# VCF.net
KiCad netlist of a schematic drawn in Altium Designer
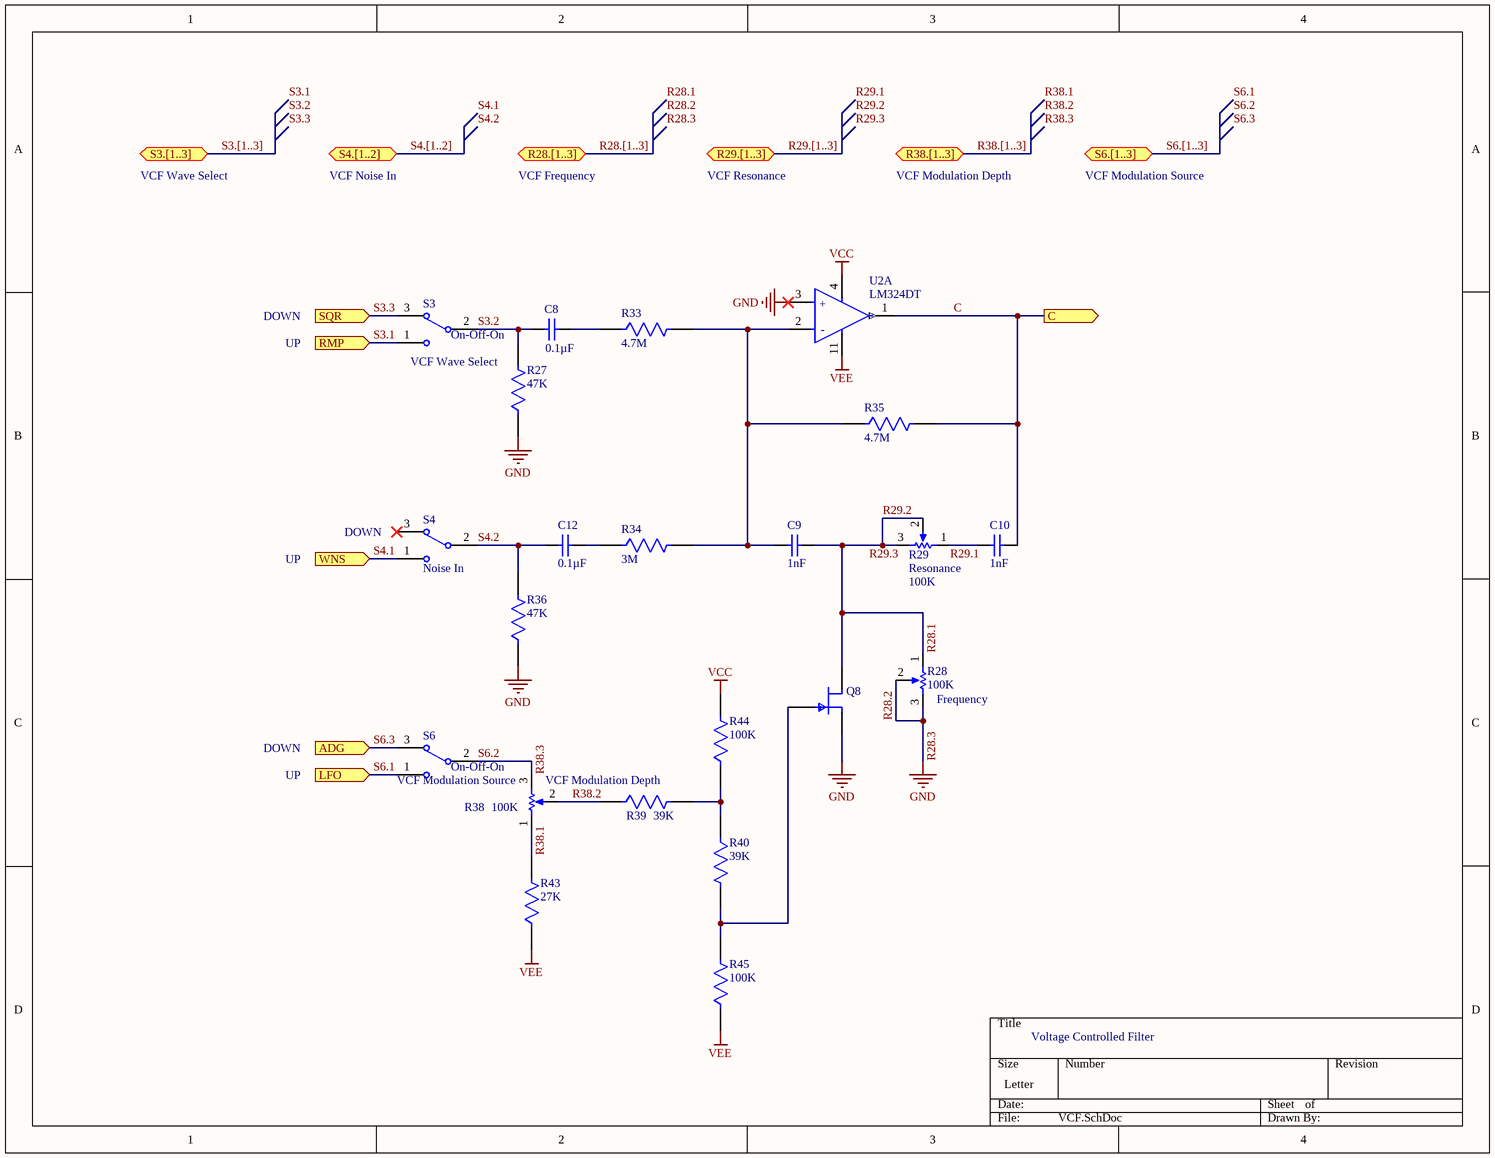
[diagram p0: VCF.SchDoc]

(export (version "E")
  (design (tool "Eeschema 10.0.6"))
  (components
    (comp (ref "C8")
      (value "CL10B104KB8NNNC")
      (footprint "SAMS-C0603-2_M")
      (description "Multi-layer Ceramic Capacitor, -55 to 125 degC, 2-Pin SMD (0603), RoHS, Tape and Reel")
      (fields (field (name "CAPACITANCE") "0.1µF") (field (name "MANUFACTURER") "Samsung Electro-Mechanics"))
      (libsource (lib "Altium Content Vault") (part "CAP-NP-2"))
    )
    (comp (ref "C9")
      (value "885012206083‎")
      (footprint "CAPC1608X90X35NL10T15")
      (fields
        (field (name "MANUFACTURER") "Wurth")
        (field (name "MANUFACTURER PART NUMBER") "885012206083")
        (field (name "CAPACITANCE") "1nF")
        (field (name "TOLERANCE") "10%")
      )
      (libsource (lib "Altium Content Vault") (part "CAP"))
    )
    (comp (ref "C10")
      (value "885012206083‎")
      (footprint "CAPC1608X90X35NL10T15")
      (fields
        (field (name "MANUFACTURER") "Wurth")
        (field (name "MANUFACTURER PART NUMBER") "885012206083")
        (field (name "CAPACITANCE") "1nF")
        (field (name "TOLERANCE") "10%")
      )
      (libsource (lib "Altium Content Vault") (part "CAP"))
    )
    (comp (ref "C12")
      (value "CL10B104KB8NNNC")
      (footprint "SAMS-C0603-2_M")
      (description "Multi-layer Ceramic Capacitor, -55 to 125 degC, 2-Pin SMD (0603), RoHS, Tape and Reel")
      (fields (field (name "CAPACITANCE") "0.1µF") (field (name "MANUFACTURER") "Samsung Electro-Mechanics"))
      (libsource (lib "Altium Content Vault") (part "CAP-NP-2"))
    )
    (comp (ref "Q8")
      (value "MMBFJ113")
      (footprint "FP-318BM-IPC_C")
      (description "JFET N-CH 35V 350MW SOT23")
      (fields
        (field (name "MANUFACTURER") "ON Semiconductor")
        (field (name "OCTOPART") "https://octopart.com/mmbfj113-on+semiconductor-84330253")
      )
      (libsource (lib "Altium Content Vault") (part "14398f7355be6f33287877db3ee21c7"))
    )
    (comp (ref "R27")
      (value "ESR03EZPJ473")
      (footprint "FP-ESR03-IPC_B")
      (description "47kΩ ±5% 0.25W 0603 Anti-Surge Chip Resistor AEC-Q200")
      (fields (field (name "RESISTANCE") "47K") (field (name "TOLERANCE") "5%"))
      (libsource (lib "Altium Content Vault") (part "1029c3af85768c4190bb7ad29bc67b5"))
    )
    (comp (ref "R28")
      (value "Frequency")
      (footprint "VR5")
      (description "Potentiometer")
      (fields (field (name "ALTIUM_VALUE") "100K") (field (name "PUBLISHER") "Altium Limited"))
      (libsource (lib "Miscellaneous Devices") (part "RPot"))
    )
    (comp (ref "R29")
      (value "Resonance")
      (footprint "VR5")
      (description "Potentiometer")
      (fields (field (name "ALTIUM_VALUE") "100K") (field (name "PUBLISHER") "Altium Limited"))
      (libsource (lib "Miscellaneous Devices") (part "RPot"))
    )
    (comp (ref "R33")
      (value "ESR03EZPJ475")
      (footprint "FP-ESR03-IPC_B")
      (description "4.7MΩ ±5% 0.25W 0603 Anti-Surge Chip Resistor AEC-Q200")
      (fields (field (name "TOLERANCE") "5%") (field (name "RESISTANCE") "4.7M"))
      (libsource (lib "Altium Content Vault") (part "1029c3af85768c4190bb7ad29bc67b5"))
    )
    (comp (ref "R34")
      (value "ESR03EZPJ305")
      (footprint "FP-ESR03-IPC_B")
      (description "3MΩ ±5% 0.25W 0603 Anti-Surge Chip Resistor AEC-Q200")
      (fields (field (name "TOLERANCE") "5%") (field (name "RESISTANCE") "3M"))
      (libsource (lib "Altium Content Vault") (part "1029c3af85768c4190bb7ad29bc67b5"))
    )
    (comp (ref "R35")
      (value "ESR03EZPJ475")
      (footprint "FP-ESR03-IPC_B")
      (description "4.7MΩ ±5% 0.25W 0603 Anti-Surge Chip Resistor AEC-Q200")
      (fields (field (name "TOLERANCE") "5%") (field (name "RESISTANCE") "4.7M"))
      (libsource (lib "Altium Content Vault") (part "1029c3af85768c4190bb7ad29bc67b5"))
    )
    (comp (ref "R36")
      (value "ESR03EZPJ473")
      (footprint "FP-ESR03-IPC_B")
      (description "47kΩ ±5% 0.25W 0603 Anti-Surge Chip Resistor AEC-Q200")
      (fields (field (name "RESISTANCE") "47K") (field (name "TOLERANCE") "5%"))
      (libsource (lib "Altium Content Vault") (part "1029c3af85768c4190bb7ad29bc67b5"))
    )
    (comp (ref "R38")
      (value "VCF Modulation Depth")
      (footprint "VR5")
      (description "Potentiometer")
      (fields (field (name "ALTIUM_VALUE") "100K") (field (name "PUBLISHER") "Altium Limited"))
      (libsource (lib "Miscellaneous Devices") (part "RPot"))
    )
    (comp (ref "R39")
      (value "ESR03EZPJ393")
      (footprint "FP-ESR03-IPC_B")
      (description "39kΩ ±5% 0.25W 0603 Anti-Surge Chip Resistor AEC-Q200")
      (fields (field (name "RESISTANCE") "39K") (field (name "TOLERANCE") "5%"))
      (libsource (lib "Altium Content Vault") (part "1029c3af85768c4190bb7ad29bc67b5"))
    )
    (comp (ref "R40")
      (value "ESR03EZPJ393")
      (footprint "FP-ESR03-IPC_B")
      (description "39kΩ ±5% 0.25W 0603 Anti-Surge Chip Resistor AEC-Q200")
      (fields (field (name "RESISTANCE") "39K") (field (name "TOLERANCE") "5%"))
      (libsource (lib "Altium Content Vault") (part "1029c3af85768c4190bb7ad29bc67b5"))
    )
    (comp (ref "R43")
      (value "ESR03EZPJ273")
      (footprint "FP-ESR03-IPC_B")
      (description "27kΩ ±5% 0.25W 0603 Anti-Surge Chip Resistor AEC-Q200")
      (fields (field (name "RESISTANCE") "27K") (field (name "TOLERANCE") "5%"))
      (libsource (lib "Altium Content Vault") (part "1029c3af85768c4190bb7ad29bc67b5"))
    )
    (comp (ref "R44")
      (value "ESR03EZPJ104")
      (footprint "FP-ESR03-IPC_B")
      (description "100kΩ ±5% 0.25W 0603 Anti-Surge Chip Resistor AEC-Q200")
      (fields (field (name "TOLERANCE") "5%") (field (name "RESISTANCE") "100K"))
      (libsource (lib "Altium Content Vault") (part "1029c3af85768c4190bb7ad29bc67b5"))
    )
    (comp (ref "R45")
      (value "ESR03EZPJ104")
      (footprint "FP-ESR03-IPC_B")
      (description "100kΩ ±5% 0.25W 0603 Anti-Surge Chip Resistor AEC-Q200")
      (fields (field (name "TOLERANCE") "5%") (field (name "RESISTANCE") "100K"))
      (libsource (lib "Altium Content Vault") (part "1029c3af85768c4190bb7ad29bc67b5"))
    )
    (comp (ref "S3")
      (value "VCF Wave Select")
      (footprint "HDR1X3")
      (description "Switch Toggle ON OFF ON SPDT Round Lever Solder Lug 5A 250VAC 28VDC Panel Mount with Threads")
      (fields
        (field (name "MANUFACTURER") "E-Switch")
        (field (name "MANUFACTURER PART NUMBER") "100SP3T1B1M1QEH")
        (field (name "SWITCH FUNCTION") "On-Off-On")
        (field (name "PUBLISHER") "Altium Limited")
      )
      (libsource (lib "Miscellaneous Devices") (part "SW-SPDT"))
    )
    (comp (ref "S4")
      (value "Noise In")
      (footprint "HDR1X3")
      (description "Switch Toggle ON None ON SPDT Round Lever Solder Lug 5A 250VAC 28VDC Panel Mount with Threads")
      (fields
        (field (name "MANUFACTURER") "E-Switch")
        (field (name "MANUFACTURER PART NUMBER") "100SP1T1B1M1QEH")
      )
      (libsource (lib "Miscellaneous Devices") (part "SW-SPDT"))
    )
    (comp (ref "S6")
      (value "VCF Modulation Source")
      (footprint "HDR1X3")
      (description "Switch Toggle ON OFF ON SPDT Round Lever Solder Lug 5A 250VAC 28VDC Panel Mount with Threads")
      (fields
        (field (name "MANUFACTURER") "E-Switch")
        (field (name "MANUFACTURER PART NUMBER") "100SP3T1B1M1QEH")
        (field (name "SWITCH FUNCTION") "On-Off-On")
        (field (name "PUBLISHER") "Altium Limited")
      )
      (libsource (lib "Miscellaneous Devices") (part "SW-SPDT"))
    )
    (comp (ref "U2")
      (value "LM324DT")
      (footprint "FP-SO-14-MFG")
      (description "IC OPAMP GP 4 CIRCUIT 14SO")
      (fields
        (field (name "OCTOPART") "https://octopart.com/lm324dt-stmicroelectronics-39579146")
        (field (name "MANUFACTURER") "STMicroelectronics")
      )
      (libsource (lib "Altium Content Vault") (part "a065ef67e5aa9ef3942d43d6008d043"))
    )
  )
  (nets
    (net (code "1") (name "/C") (class "Default")
      (node (ref "C10") (pin "2") (pinfunction "2_2") (pintype "passive"))
      (node (ref "R35") (pin "2") (pinfunction "2_2") (pintype "passive"))
      (node (ref "U2") (pin "1") (pinfunction "Output_1_1") (pintype "output"))
    )
    (net (code "3") (name "/R29.1") (class "Default")
      (node (ref "C10") (pin "1") (pinfunction "1_1") (pintype "passive"))
      (node (ref "R29") (pin "1") (pinfunction "TOP_1") (pintype "passive"))
    )
    (net (code "4") (name "/R29.3") (class "Default")
      (node (ref "C9") (pin "2") (pinfunction "2_2") (pintype "passive"))
      (node (ref "Q8") (pin "1") (pinfunction "D_1") (pintype "passive"))
      (node (ref "R28") (pin "1") (pinfunction "TOP_1") (pintype "passive"))
      (node (ref "R29") (pin "2") (pinfunction "TAP_2") (pintype "passive"))
      (node (ref "R29") (pin "3") (pinfunction "BOT_3") (pintype "passive"))
    )
    (net (code "6") (name "/R38.1") (class "Default")
      (node (ref "R38") (pin "1") (pinfunction "TOP_1") (pintype "passive"))
      (node (ref "R43") (pin "2") (pinfunction "2_2") (pintype "passive"))
    )
    (net (code "7") (name "/R38.2") (class "Default")
      (node (ref "R38") (pin "2") (pinfunction "TAP_2") (pintype "passive"))
      (node (ref "R39") (pin "1") (pinfunction "1_1") (pintype "passive"))
    )
    (net (code "9") (name "/S3.1") (class "Default")
      (node (ref "S3") (pin "1") (pinfunction "1_1") (pintype "passive"))
    )
    (net (code "10") (name "/S3.2") (class "Default")
      (node (ref "C8") (pin "1") (pinfunction "1_1") (pintype "passive"))
      (node (ref "R27") (pin "2") (pinfunction "2_2") (pintype "passive"))
      (node (ref "S3") (pin "2") (pinfunction "2_2") (pintype "passive"))
    )
    (net (code "11") (name "/S3.3") (class "Default")
      (node (ref "S3") (pin "3") (pinfunction "3_3") (pintype "passive"))
    )
    (net (code "13") (name "/S4.1") (class "Default")
      (node (ref "S4") (pin "1") (pinfunction "1_1") (pintype "passive"))
    )
    (net (code "14") (name "/S4.2") (class "Default")
      (node (ref "C12") (pin "1") (pinfunction "1_1") (pintype "passive"))
      (node (ref "R36") (pin "2") (pinfunction "2_2") (pintype "passive"))
      (node (ref "S4") (pin "2") (pinfunction "2_2") (pintype "passive"))
    )
    (net (code "16") (name "/S6.1") (class "Default")
      (node (ref "S6") (pin "1") (pinfunction "1_1") (pintype "passive"))
    )
    (net (code "17") (name "/S6.2") (class "Default")
      (node (ref "R38") (pin "3") (pinfunction "BOT_3") (pintype "passive"))
      (node (ref "S6") (pin "2") (pinfunction "2_2") (pintype "passive"))
    )
    (net (code "18") (name "/S6.3") (class "Default")
      (node (ref "S6") (pin "3") (pinfunction "3_3") (pintype "passive"))
    )
    (net (code "20") (name "GND") (class "Default")
      (node (ref "Q8") (pin "2") (pinfunction "S_2") (pintype "passive"))
      (node (ref "R27") (pin "1") (pinfunction "1_1") (pintype "passive"))
      (node (ref "R28") (pin "2") (pinfunction "TAP_2") (pintype "passive"))
      (node (ref "R28") (pin "3") (pinfunction "BOT_3") (pintype "passive"))
      (node (ref "R36") (pin "1") (pinfunction "1_1") (pintype "passive"))
      (node (ref "U2") (pin "3") (pinfunction "Non-Inverting_Input_1_3") (pintype "tri_state"))
    )
    (net (code "21") (name "Net-(C8-Pad2)") (class "Default")
      (node (ref "C8") (pin "2") (pinfunction "2_2") (pintype "passive"))
      (node (ref "R33") (pin "1") (pinfunction "1_1") (pintype "passive"))
    )
    (net (code "22") (name "Net-(C12-Pad2)") (class "Default")
      (node (ref "C12") (pin "2") (pinfunction "2_2") (pintype "passive"))
      (node (ref "R34") (pin "1") (pinfunction "1_1") (pintype "passive"))
    )
    (net (code "23") (name "Net-(Q8-G)") (class "Default")
      (node (ref "Q8") (pin "3") (pinfunction "G_3") (pintype "passive"))
      (node (ref "R40") (pin "2") (pinfunction "2_2") (pintype "passive"))
      (node (ref "R45") (pin "2") (pinfunction "2_2") (pintype "passive"))
    )
    (net (code "24") (name "Net-(R39-Pad2)") (class "Default")
      (node (ref "R39") (pin "2") (pinfunction "2_2") (pintype "passive"))
      (node (ref "R40") (pin "1") (pinfunction "1_1") (pintype "passive"))
      (node (ref "R44") (pin "1") (pinfunction "1_1") (pintype "passive"))
    )
    (net (code "25") (name "Net-(U2A-Inverting_Input_1)") (class "Default")
      (node (ref "C9") (pin "1") (pinfunction "1_1") (pintype "passive"))
      (node (ref "R33") (pin "2") (pinfunction "2_2") (pintype "passive"))
      (node (ref "R34") (pin "2") (pinfunction "2_2") (pintype "passive"))
      (node (ref "R35") (pin "1") (pinfunction "1_1") (pintype "passive"))
      (node (ref "U2") (pin "2") (pinfunction "Inverting_Input_1_2") (pintype "tri_state"))
    )
    (net (code "26") (name "VCC") (class "Default")
      (node (ref "R44") (pin "2") (pinfunction "2_2") (pintype "passive"))
      (node (ref "U2") (pin "4") (pinfunction "VCC+_4") (pintype "power_in"))
    )
    (net (code "27") (name "VEE") (class "Default")
      (node (ref "R43") (pin "1") (pinfunction "1_1") (pintype "passive"))
      (node (ref "R45") (pin "1") (pinfunction "1_1") (pintype "passive"))
      (node (ref "U2") (pin "11") (pinfunction "VCC-_11") (pintype "power_in"))
    )
    (net (code "28") (name "unconnected-(S4-Pad3)") (class "Default")
      (node (ref "S4") (pin "3") (pinfunction "3_3") (pintype "passive+no_connect"))
    )
  )
)
